# ATMega64_Breakout.net
KiCad netlist of a schematic drawn in Altium Designer
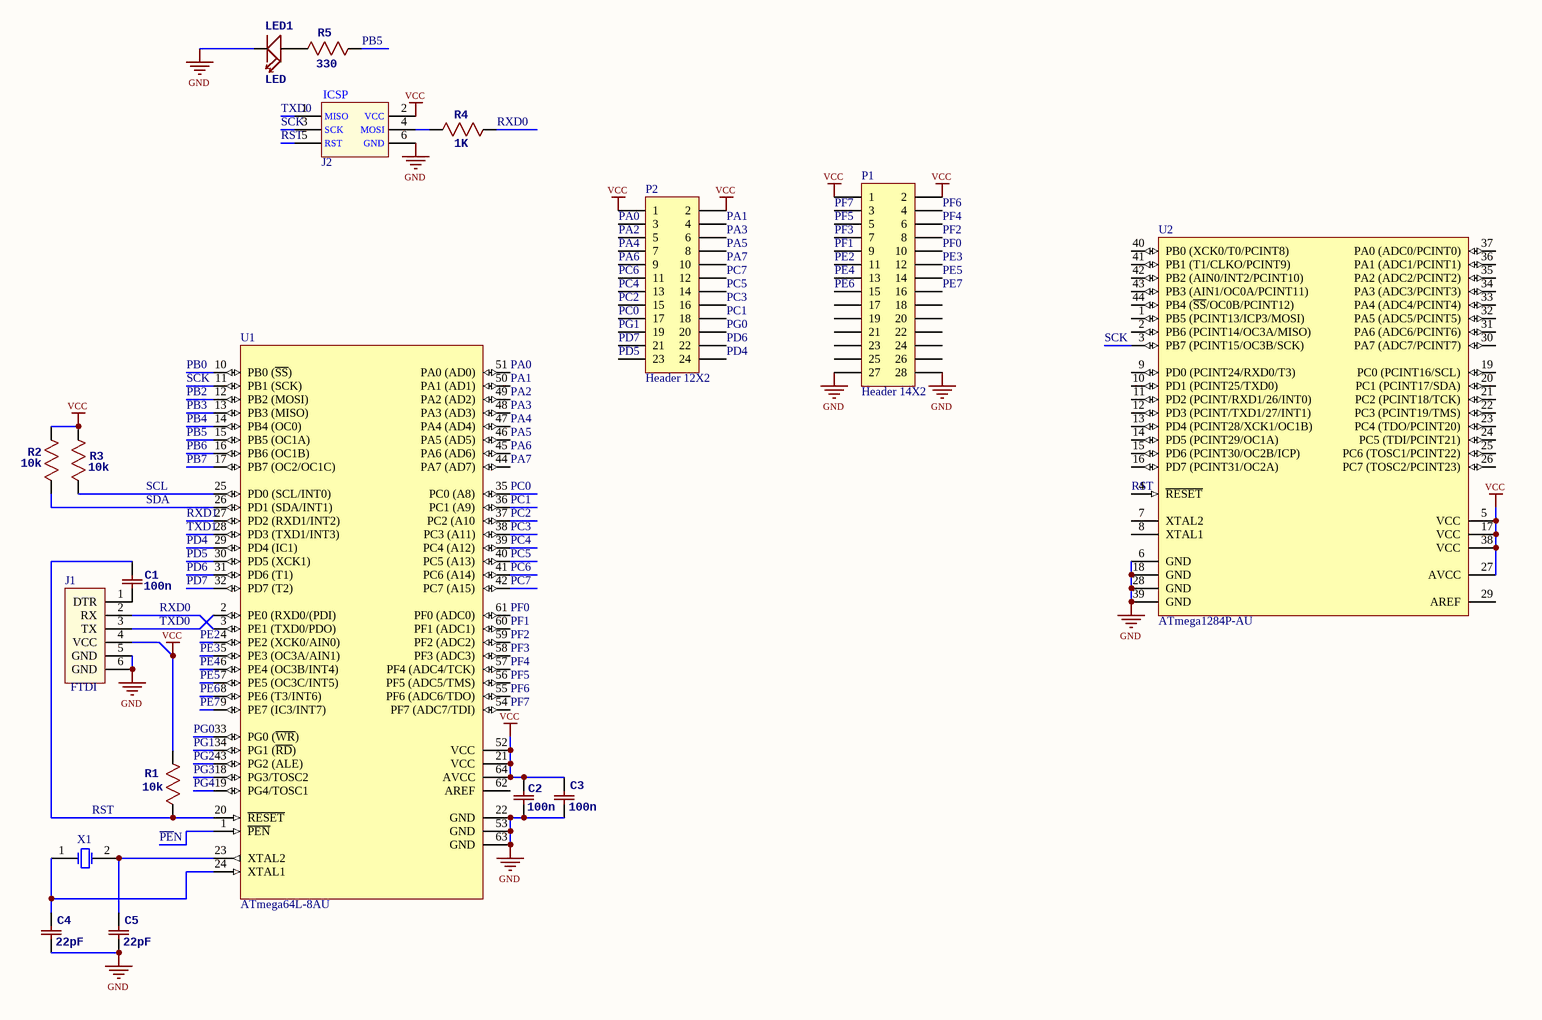
[diagram p0: ATMega64_Breakout.SchDoc]

(export (version "E")
  (design (tool "Eeschema 10.0.6"))
  (components
    (comp (ref "C1")
      (value "100n")
      (footprint "CAPC0805(2012)75_N")
      (fields (field (name "MPN") "U0805F104ZCT") (field (name "TOLERANCE") "-20/+80%"))
      (libsource (lib "Multicomp_By_element14_Batch_1") (part "U0805F104ZCT"))
    )
    (comp (ref "C2")
      (value "100n")
      (footprint "CAPC0805(2012)75_N")
      (fields (field (name "MPN") "U0805F104ZCT") (field (name "TOLERANCE") "-20/+80%"))
      (libsource (lib "Multicomp_By_element14_Batch_1") (part "U0805F104ZCT"))
    )
    (comp (ref "C3")
      (value "100n")
      (footprint "CAPC0805(2012)75_N")
      (fields (field (name "MPN") "U0805F104ZCT") (field (name "TOLERANCE") "-20/+80%"))
      (libsource (lib "Multicomp_By_element14_Batch_1") (part "U0805F104ZCT"))
    )
    (comp (ref "C4")
      (value "22pF")
      (footprint "CAPC0805(2012)75_N")
      (fields (field (name "MPN") "U0805F104ZCT") (field (name "TOLERANCE") "-20/+80%"))
      (libsource (lib "Multicomp_By_element14_Batch_1") (part "U0805F104ZCT"))
    )
    (comp (ref "C5")
      (value "22pF")
      (footprint "CAPC0805(2012)75_N")
      (fields (field (name "MPN") "U0805F104ZCT") (field (name "TOLERANCE") "-20/+80%"))
      (libsource (lib "Multicomp_By_element14_Batch_1") (part "U0805F104ZCT"))
    )
    (comp (ref "J1")
      (value "FTDI")
      (footprint "HDR1X6")
      (description "In-Circuit Serial Programming Header")
      (libsource (lib "AltiumIntegratedLibrary") (part "ICSP"))
    )
    (comp (ref "J2")
      (value "ICSP")
      (footprint "ICSP")
      (description "AVR ICSP")
      (libsource (lib "") (part "ICSP_1"))
    )
    (comp (ref "LED1")
      (value "LED")
      (footprint "LED-0805")
      (fields (field (name "MPN") "17-215SURC/S530-A2/TR8"))
      (libsource (lib "105848_revD3") (part "SMD-LED-CLEAR-RED(0805)"))
    )
    (comp (ref "P1")
      (value "Header 14X2")
      (footprint "HDR2X14")
      (description "Header, 14-Pin, Dual row")
      (fields (field (name "PUBLISHER") "Altium Limited"))
      (libsource (lib "Miscellaneous Connectors") (part "Header 14X2"))
    )
    (comp (ref "P2")
      (value "Header 12X2")
      (footprint "HDR2X12")
      (description "Header, 12-Pin, Dual row")
      (fields (field (name "PUBLISHER") "Altium Limited"))
      (libsource (lib "Miscellaneous Connectors") (part "Header 12X2"))
    )
    (comp (ref "R1")
      (value "10k")
      (footprint "RCHIP0805")
      (fields (field (name "MPN") "MC0.1W08051%10K") (field (name "TOLERANCE") "±1%"))
      (libsource (lib "Multicomp_By_element14_Batch_1") (part "MC0.1W08051%10K"))
    )
    (comp (ref "R2")
      (value "10k")
      (footprint "RCHIP0805")
      (fields (field (name "MPN") "MC0.1W08051%10K") (field (name "TOLERANCE") "±1%"))
      (libsource (lib "Multicomp_By_element14_Batch_1") (part "MC0.1W08051%10K"))
    )
    (comp (ref "R3")
      (value "10k")
      (footprint "RCHIP0805")
      (fields (field (name "MPN") "MC0.1W08051%10K") (field (name "TOLERANCE") "±1%"))
      (libsource (lib "Multicomp_By_element14_Batch_1") (part "MC0.1W08051%10K"))
    )
    (comp (ref "R4")
      (value "1K")
      (footprint "RCHIP0805")
      (fields (field (name "MPN") "MC0.1W08051%1K") (field (name "TOLERANCE") "±1%"))
      (libsource (lib "Multicomp_By_element14_Batch_1") (part "MC0.1W08051%1K"))
    )
    (comp (ref "R5")
      (value "330")
      (footprint "RCHIP0805")
      (fields (field (name "MPN") "MC0.1W08051%1K") (field (name "TOLERANCE") "±1%"))
      (libsource (lib "Multicomp_By_element14_Batch_1") (part "MC0.1W08051%1K"))
    )
    (comp (ref "U1")
      (value "ATmega64L-8AU")
      (footprint "64A_M")
      (libsource (lib "Atmel Microcontroller megaAVR") (part "ATmega64L-8AU"))
    )
    (comp (ref "U2")
      (value "ATmega1284P-AU")
      (footprint "44A_L")
      (libsource (lib "Atmel Microcontroller megaAVR") (part "ATmega1284P-AU"))
    )
    (comp (ref "X1")
      (value "XTAL")
      (footprint "CRES_SMT")
      (description "Crystal Oscillator")
      (fields (field (name "PUBLISHER") "Altium Limited"))
      (libsource (lib "Miscellaneous Devices") (part "XTAL"))
    )
  )
  (nets
    (net (code "1") (name "/PA0") (class "Default")
      (node (ref "P2") (pin "3") (pinfunction "3_3") (pintype "passive"))
      (node (ref "U1") (pin "51") (pinfunction "PA0_(AD0)_51") (pintype "bidirectional"))
    )
    (net (code "2") (name "/PA1") (class "Default")
      (node (ref "P2") (pin "4") (pinfunction "4_4") (pintype "passive"))
      (node (ref "U1") (pin "50") (pinfunction "PA1_(AD1)_50") (pintype "bidirectional"))
    )
    (net (code "3") (name "/PA2") (class "Default")
      (node (ref "P2") (pin "5") (pinfunction "5_5") (pintype "passive"))
      (node (ref "U1") (pin "49") (pinfunction "PA2_(AD2)_49") (pintype "bidirectional"))
    )
    (net (code "4") (name "/PA3") (class "Default")
      (node (ref "P2") (pin "6") (pinfunction "6_6") (pintype "passive"))
      (node (ref "U1") (pin "48") (pinfunction "PA3_(AD3)_48") (pintype "bidirectional"))
    )
    (net (code "5") (name "/PA4") (class "Default")
      (node (ref "P2") (pin "7") (pinfunction "7_7") (pintype "passive"))
      (node (ref "U1") (pin "47") (pinfunction "PA4_(AD4)_47") (pintype "bidirectional"))
    )
    (net (code "6") (name "/PA5") (class "Default")
      (node (ref "P2") (pin "8") (pinfunction "8_8") (pintype "passive"))
      (node (ref "U1") (pin "46") (pinfunction "PA5_(AD5)_46") (pintype "bidirectional"))
    )
    (net (code "7") (name "/PA6") (class "Default")
      (node (ref "P2") (pin "9") (pinfunction "9_9") (pintype "passive"))
      (node (ref "U1") (pin "45") (pinfunction "PA6_(AD6)_45") (pintype "bidirectional"))
    )
    (net (code "8") (name "/PA7") (class "Default")
      (node (ref "P2") (pin "10") (pinfunction "10_10") (pintype "passive"))
      (node (ref "U1") (pin "44") (pinfunction "PA7_(AD7)_44") (pintype "bidirectional"))
    )
    (net (code "9") (name "/PB0") (class "Default")
      (node (ref "U1") (pin "10") (pinfunction "PB0_(~{SS})_10") (pintype "bidirectional"))
    )
    (net (code "10") (name "/PB2") (class "Default")
      (node (ref "U1") (pin "12") (pinfunction "PB2_(MOSI)_12") (pintype "bidirectional"))
    )
    (net (code "11") (name "/PB3") (class "Default")
      (node (ref "U1") (pin "13") (pinfunction "PB3_(MISO)_13") (pintype "bidirectional"))
    )
    (net (code "12") (name "/PB4") (class "Default")
      (node (ref "U1") (pin "14") (pinfunction "PB4_(OC0)_14") (pintype "bidirectional"))
    )
    (net (code "13") (name "/PB5") (class "Default")
      (node (ref "R5") (pin "2") (pinfunction "R2_2") (pintype "passive"))
      (node (ref "U1") (pin "15") (pinfunction "PB5_(OC1A)_15") (pintype "bidirectional"))
    )
    (net (code "14") (name "/PB6") (class "Default")
      (node (ref "U1") (pin "16") (pinfunction "PB6_(OC1B)_16") (pintype "bidirectional"))
    )
    (net (code "15") (name "/PB7") (class "Default")
      (node (ref "U1") (pin "17") (pinfunction "PB7_(OC2/OC1C)_17") (pintype "bidirectional"))
    )
    (net (code "16") (name "/PC0") (class "Default")
      (node (ref "P2") (pin "17") (pinfunction "17_17") (pintype "passive"))
      (node (ref "U1") (pin "35") (pinfunction "PC0_(A8)_35") (pintype "bidirectional"))
    )
    (net (code "17") (name "/PC1") (class "Default")
      (node (ref "P2") (pin "18") (pinfunction "18_18") (pintype "passive"))
      (node (ref "U1") (pin "36") (pinfunction "PC1_(A9)_36") (pintype "bidirectional"))
    )
    (net (code "18") (name "/PC2") (class "Default")
      (node (ref "P2") (pin "15") (pinfunction "15_15") (pintype "passive"))
      (node (ref "U1") (pin "37") (pinfunction "PC2_(A10_37") (pintype "bidirectional"))
    )
    (net (code "19") (name "/PC3") (class "Default")
      (node (ref "P2") (pin "16") (pinfunction "16_16") (pintype "passive"))
      (node (ref "U1") (pin "38") (pinfunction "PC3_(A11)_38") (pintype "bidirectional"))
    )
    (net (code "20") (name "/PC4") (class "Default")
      (node (ref "P2") (pin "13") (pinfunction "13_13") (pintype "passive"))
      (node (ref "U1") (pin "39") (pinfunction "PC4_(A12)_39") (pintype "bidirectional"))
    )
    (net (code "21") (name "/PC5") (class "Default")
      (node (ref "P2") (pin "14") (pinfunction "14_14") (pintype "passive"))
      (node (ref "U1") (pin "40") (pinfunction "PC5_(A13)_40") (pintype "bidirectional"))
    )
    (net (code "22") (name "/PC6") (class "Default")
      (node (ref "P2") (pin "11") (pinfunction "11_11") (pintype "passive"))
      (node (ref "U1") (pin "41") (pinfunction "PC6_(A14)_41") (pintype "bidirectional"))
    )
    (net (code "23") (name "/PC7") (class "Default")
      (node (ref "P2") (pin "12") (pinfunction "12_12") (pintype "passive"))
      (node (ref "U1") (pin "42") (pinfunction "PC7_(A15)_42") (pintype "bidirectional"))
    )
    (net (code "24") (name "/PD4") (class "Default")
      (node (ref "P2") (pin "24") (pinfunction "24_24") (pintype "passive"))
      (node (ref "U1") (pin "29") (pinfunction "PD4_(IC1)_29") (pintype "bidirectional"))
    )
    (net (code "25") (name "/PD5") (class "Default")
      (node (ref "P2") (pin "23") (pinfunction "23_23") (pintype "passive"))
      (node (ref "U1") (pin "30") (pinfunction "PD5_(XCK1)_30") (pintype "bidirectional"))
    )
    (net (code "26") (name "/PD6") (class "Default")
      (node (ref "P2") (pin "22") (pinfunction "22_22") (pintype "passive"))
      (node (ref "U1") (pin "31") (pinfunction "PD6_(T1)_31") (pintype "bidirectional"))
    )
    (net (code "27") (name "/PD7") (class "Default")
      (node (ref "P2") (pin "21") (pinfunction "21_21") (pintype "passive"))
      (node (ref "U1") (pin "32") (pinfunction "PD7_(T2)_32") (pintype "bidirectional"))
    )
    (net (code "28") (name "/PE2") (class "Default")
      (node (ref "P1") (pin "11") (pinfunction "11_11") (pintype "passive"))
      (node (ref "U1") (pin "4") (pinfunction "PE2_(XCK0/AIN0)_4") (pintype "bidirectional"))
    )
    (net (code "29") (name "/PE3") (class "Default")
      (node (ref "P1") (pin "12") (pinfunction "12_12") (pintype "passive"))
      (node (ref "U1") (pin "5") (pinfunction "PE3_(OC3A/AIN1)_5") (pintype "bidirectional"))
    )
    (net (code "30") (name "/PE4") (class "Default")
      (node (ref "P1") (pin "13") (pinfunction "13_13") (pintype "passive"))
      (node (ref "U1") (pin "6") (pinfunction "PE4_(OC3B/INT4)_6") (pintype "bidirectional"))
    )
    (net (code "31") (name "/PE5") (class "Default")
      (node (ref "P1") (pin "14") (pinfunction "14_14") (pintype "passive"))
      (node (ref "U1") (pin "7") (pinfunction "PE5_(OC3C/INT5)_7") (pintype "bidirectional"))
    )
    (net (code "32") (name "/PE6") (class "Default")
      (node (ref "P1") (pin "15") (pinfunction "15_15") (pintype "passive"))
      (node (ref "U1") (pin "8") (pinfunction "PE6_(T3/INT6)_8") (pintype "bidirectional"))
    )
    (net (code "33") (name "/PE7") (class "Default")
      (node (ref "P1") (pin "16") (pinfunction "16_16") (pintype "passive"))
      (node (ref "U1") (pin "9") (pinfunction "PE7_(IC3/INT7)_9") (pintype "bidirectional"))
    )
    (net (code "34") (name "/PF0") (class "Default")
      (node (ref "P1") (pin "10") (pinfunction "10_10") (pintype "passive"))
      (node (ref "U1") (pin "61") (pinfunction "PF0_(ADC0)_61") (pintype "bidirectional"))
    )
    (net (code "35") (name "/PF1") (class "Default")
      (node (ref "P1") (pin "9") (pinfunction "9_9") (pintype "passive"))
      (node (ref "U1") (pin "60") (pinfunction "PF1_(ADC1)_60") (pintype "bidirectional"))
    )
    (net (code "36") (name "/PF2") (class "Default")
      (node (ref "P1") (pin "8") (pinfunction "8_8") (pintype "passive"))
      (node (ref "U1") (pin "59") (pinfunction "PF2_(ADC2)_59") (pintype "bidirectional"))
    )
    (net (code "37") (name "/PF3") (class "Default")
      (node (ref "P1") (pin "7") (pinfunction "7_7") (pintype "passive"))
      (node (ref "U1") (pin "58") (pinfunction "PF3_(ADC3)_58") (pintype "bidirectional"))
    )
    (net (code "38") (name "/PF4") (class "Default")
      (node (ref "P1") (pin "6") (pinfunction "6_6") (pintype "passive"))
      (node (ref "U1") (pin "57") (pinfunction "PF4_(ADC4/TCK)_57") (pintype "bidirectional"))
    )
    (net (code "39") (name "/PF5") (class "Default")
      (node (ref "P1") (pin "5") (pinfunction "5_5") (pintype "passive"))
      (node (ref "U1") (pin "56") (pinfunction "PF5_(ADC5/TMS)_56") (pintype "bidirectional"))
    )
    (net (code "40") (name "/PF6") (class "Default")
      (node (ref "P1") (pin "4") (pinfunction "4_4") (pintype "passive"))
      (node (ref "U1") (pin "55") (pinfunction "PF6_(ADC6/TDO)_55") (pintype "bidirectional"))
    )
    (net (code "41") (name "/PF7") (class "Default")
      (node (ref "P1") (pin "3") (pinfunction "3_3") (pintype "passive"))
      (node (ref "U1") (pin "54") (pinfunction "PF7_(ADC7/TDI)_54") (pintype "bidirectional"))
    )
    (net (code "42") (name "/PG0") (class "Default")
      (node (ref "P2") (pin "20") (pinfunction "20_20") (pintype "passive"))
      (node (ref "U1") (pin "33") (pinfunction "PG0_(~{WR})_33") (pintype "bidirectional"))
    )
    (net (code "43") (name "/PG1") (class "Default")
      (node (ref "P2") (pin "19") (pinfunction "19_19") (pintype "passive"))
      (node (ref "U1") (pin "34") (pinfunction "PG1_(~{RD})_34") (pintype "bidirectional"))
    )
    (net (code "44") (name "/PG2") (class "Default")
      (node (ref "U1") (pin "43") (pinfunction "PG2_(ALE)_43") (pintype "bidirectional"))
    )
    (net (code "45") (name "/PG3") (class "Default")
      (node (ref "U1") (pin "18") (pinfunction "PG3/TOSC2_18") (pintype "bidirectional"))
    )
    (net (code "46") (name "/PG4") (class "Default")
      (node (ref "U1") (pin "19") (pinfunction "PG4/TOSC1_19") (pintype "bidirectional"))
    )
    (net (code "47") (name "/RST") (class "Default")
      (node (ref "C1") (pin "2") (pinfunction "C2_2") (pintype "passive"))
      (node (ref "J2") (pin "5") (pinfunction "RST_5") (pintype "passive"))
      (node (ref "R1") (pin "2") (pinfunction "R2_2") (pintype "passive"))
      (node (ref "U1") (pin "20") (pinfunction "~{RESET}_20") (pintype "input"))
      (node (ref "U2") (pin "4") (pinfunction "~{RESET}_4") (pintype "input"))
    )
    (net (code "48") (name "/RXD0") (class "Default")
      (node (ref "J1") (pin "2") (pinfunction "RX_2") (pintype "passive"))
      (node (ref "R4") (pin "1") (pinfunction "R1_1") (pintype "passive"))
      (node (ref "U1") (pin "3") (pinfunction "PE1_(TXD0/PDO)_3") (pintype "bidirectional"))
    )
    (net (code "49") (name "/RXD1") (class "Default")
      (node (ref "U1") (pin "27") (pinfunction "PD2_(RXD1/INT2)_27") (pintype "bidirectional"))
    )
    (net (code "50") (name "/SCK") (class "Default")
      (node (ref "J2") (pin "3") (pinfunction "SCK_3") (pintype "passive"))
      (node (ref "U1") (pin "11") (pinfunction "PB1_(SCK)_11") (pintype "bidirectional"))
      (node (ref "U2") (pin "3") (pinfunction "PB7_(PCINT15/OC3B/SCK)_3") (pintype "bidirectional"))
    )
    (net (code "51") (name "/SCL") (class "Default")
      (node (ref "R3") (pin "2") (pinfunction "R2_2") (pintype "passive"))
      (node (ref "U1") (pin "25") (pinfunction "PD0_(SCL/INT0)_25") (pintype "bidirectional"))
    )
    (net (code "52") (name "/SDA") (class "Default")
      (node (ref "R2") (pin "2") (pinfunction "R2_2") (pintype "passive"))
      (node (ref "U1") (pin "26") (pinfunction "PD1_(SDA/INT1)_26") (pintype "bidirectional"))
    )
    (net (code "53") (name "/TXD0") (class "Default")
      (node (ref "J1") (pin "3") (pinfunction "TX_3") (pintype "passive"))
      (node (ref "J2") (pin "1") (pinfunction "MISO_1") (pintype "passive"))
      (node (ref "U1") (pin "2") (pinfunction "PE0_(RXD0/(PDI)_2") (pintype "bidirectional"))
    )
    (net (code "54") (name "/TXD1") (class "Default")
      (node (ref "U1") (pin "28") (pinfunction "PD3_(TXD1/INT3)_28") (pintype "bidirectional"))
    )
    (net (code "55") (name "/~{PE}N") (class "Default")
      (node (ref "U1") (pin "1") (pinfunction "~{PEN}_1") (pintype "input"))
    )
    (net (code "56") (name "GND") (class "Default")
      (node (ref "C2") (pin "1") (pinfunction "C1_1") (pintype "passive"))
      (node (ref "C3") (pin "1") (pinfunction "C1_1") (pintype "passive"))
      (node (ref "C4") (pin "1") (pinfunction "C1_1") (pintype "passive"))
      (node (ref "C5") (pin "1") (pinfunction "C1_1") (pintype "passive"))
      (node (ref "J1") (pin "5") (pinfunction "GND_5") (pintype "passive"))
      (node (ref "J1") (pin "6") (pinfunction "GND_6") (pintype "passive"))
      (node (ref "J2") (pin "6") (pinfunction "GND_6") (pintype "passive"))
      (node (ref "LED1") (pin "-") (pinfunction "-_-") (pintype "passive"))
      (node (ref "P1") (pin "27") (pinfunction "27_27") (pintype "passive"))
      (node (ref "P1") (pin "28") (pinfunction "28_28") (pintype "passive"))
      (node (ref "U1") (pin "22") (pinfunction "GND_22") (pintype "power_in"))
      (node (ref "U1") (pin "53") (pinfunction "GND_53") (pintype "power_in"))
      (node (ref "U1") (pin "63") (pinfunction "GND_63") (pintype "power_in"))
      (node (ref "U2") (pin "18") (pinfunction "GND_18") (pintype "power_in"))
      (node (ref "U2") (pin "28") (pinfunction "GND_28") (pintype "power_in"))
      (node (ref "U2") (pin "39") (pinfunction "GND_39") (pintype "power_in"))
      (node (ref "U2") (pin "6") (pinfunction "GND_6") (pintype "power_in"))
    )
    (net (code "57") (name "Net-(C1-C1)") (class "Default")
      (node (ref "C1") (pin "1") (pinfunction "C1_1") (pintype "passive"))
      (node (ref "J1") (pin "1") (pinfunction "DTR_1") (pintype "passive"))
    )
    (net (code "58") (name "Net-(C4-C2)") (class "Default")
      (node (ref "C4") (pin "2") (pinfunction "C2_2") (pintype "passive"))
      (node (ref "U1") (pin "24") (pinfunction "XTAL1_24") (pintype "input"))
      (node (ref "X1") (pin "1") (pinfunction "OSC1_1") (pintype "passive"))
    )
    (net (code "59") (name "Net-(C5-C2)") (class "Default")
      (node (ref "C5") (pin "2") (pinfunction "C2_2") (pintype "passive"))
      (node (ref "U1") (pin "23") (pinfunction "XTAL2_23") (pintype "output"))
      (node (ref "X1") (pin "2") (pinfunction "OSC2_2") (pintype "passive"))
    )
    (net (code "60") (name "Net-(J2-MOSI)") (class "Default")
      (node (ref "J2") (pin "4") (pinfunction "MOSI_4") (pintype "passive"))
      (node (ref "R4") (pin "2") (pinfunction "R2_2") (pintype "passive"))
    )
    (net (code "61") (name "Net-(R5-R1)") (class "Default")
      (node (ref "LED1") (pin "+") (pinfunction "+_+") (pintype "passive"))
      (node (ref "R5") (pin "1") (pinfunction "R1_1") (pintype "passive"))
    )
    (net (code "62") (name "VCC") (class "Default")
      (node (ref "C2") (pin "2") (pinfunction "C2_2") (pintype "passive"))
      (node (ref "C3") (pin "2") (pinfunction "C2_2") (pintype "passive"))
      (node (ref "J1") (pin "4") (pinfunction "VCC_4") (pintype "passive"))
      (node (ref "J2") (pin "2") (pinfunction "VCC_2") (pintype "passive"))
      (node (ref "P1") (pin "1") (pinfunction "1_1") (pintype "passive"))
      (node (ref "P1") (pin "2") (pinfunction "2_2") (pintype "passive"))
      (node (ref "P2") (pin "1") (pinfunction "1_1") (pintype "passive"))
      (node (ref "P2") (pin "2") (pinfunction "2_2") (pintype "passive"))
      (node (ref "R1") (pin "1") (pinfunction "R1_1") (pintype "passive"))
      (node (ref "R2") (pin "1") (pinfunction "R1_1") (pintype "passive"))
      (node (ref "R3") (pin "1") (pinfunction "R1_1") (pintype "passive"))
      (node (ref "U1") (pin "21") (pinfunction "VCC_21") (pintype "power_in"))
      (node (ref "U1") (pin "52") (pinfunction "VCC_52") (pintype "power_in"))
      (node (ref "U1") (pin "64") (pinfunction "AVCC_64") (pintype "power_in"))
      (node (ref "U2") (pin "17") (pinfunction "VCC_17") (pintype "power_in"))
      (node (ref "U2") (pin "27") (pinfunction "AVCC_27") (pintype "power_in"))
      (node (ref "U2") (pin "38") (pinfunction "VCC_38") (pintype "power_in"))
      (node (ref "U2") (pin "5") (pinfunction "VCC_5") (pintype "power_in"))
    )
    (net (code "63") (name "unconnected-(P1-Pad17)") (class "Default")
      (node (ref "P1") (pin "17") (pinfunction "17_17") (pintype "passive"))
    )
    (net (code "64") (name "unconnected-(P1-Pad18)") (class "Default")
      (node (ref "P1") (pin "18") (pinfunction "18_18") (pintype "passive"))
    )
    (net (code "65") (name "unconnected-(P1-Pad19)") (class "Default")
      (node (ref "P1") (pin "19") (pinfunction "19_19") (pintype "passive"))
    )
    (net (code "66") (name "unconnected-(P1-Pad20)") (class "Default")
      (node (ref "P1") (pin "20") (pinfunction "20_20") (pintype "passive"))
    )
    (net (code "67") (name "unconnected-(P1-Pad21)") (class "Default")
      (node (ref "P1") (pin "21") (pinfunction "21_21") (pintype "passive"))
    )
    (net (code "68") (name "unconnected-(P1-Pad22)") (class "Default")
      (node (ref "P1") (pin "22") (pinfunction "22_22") (pintype "passive"))
    )
    (net (code "69") (name "unconnected-(P1-Pad23)") (class "Default")
      (node (ref "P1") (pin "23") (pinfunction "23_23") (pintype "passive"))
    )
    (net (code "70") (name "unconnected-(P1-Pad24)") (class "Default")
      (node (ref "P1") (pin "24") (pinfunction "24_24") (pintype "passive"))
    )
    (net (code "71") (name "unconnected-(P1-Pad25)") (class "Default")
      (node (ref "P1") (pin "25") (pinfunction "25_25") (pintype "passive"))
    )
    (net (code "72") (name "unconnected-(P1-Pad26)") (class "Default")
      (node (ref "P1") (pin "26") (pinfunction "26_26") (pintype "passive"))
    )
    (net (code "73") (name "unconnected-(U1-AREF-Pad62)") (class "Default")
      (node (ref "U1") (pin "62") (pinfunction "AREF_62") (pintype "passive"))
    )
    (net (code "74") (name "unconnected-(U2-AREF-Pad29)") (class "Default")
      (node (ref "U2") (pin "29") (pinfunction "AREF_29") (pintype "power_in"))
    )
    (net (code "75") (name "unconnected-(U2-PA0_(ADC0{slash}PCINT0)-Pad37)") (class "Default")
      (node (ref "U2") (pin "37") (pinfunction "PA0_(ADC0/PCINT0)_37") (pintype "bidirectional"))
    )
    (net (code "76") (name "unconnected-(U2-PA1_(ADC1{slash}PCINT1)-Pad36)") (class "Default")
      (node (ref "U2") (pin "36") (pinfunction "PA1_(ADC1/PCINT1)_36") (pintype "bidirectional"))
    )
    (net (code "77") (name "unconnected-(U2-PA2_(ADC2{slash}PCINT2)-Pad35)") (class "Default")
      (node (ref "U2") (pin "35") (pinfunction "PA2_(ADC2/PCINT2)_35") (pintype "bidirectional"))
    )
    (net (code "78") (name "unconnected-(U2-PA3_(ADC3{slash}PCINT3)-Pad34)") (class "Default")
      (node (ref "U2") (pin "34") (pinfunction "PA3_(ADC3/PCINT3)_34") (pintype "bidirectional"))
    )
    (net (code "79") (name "unconnected-(U2-PA4_(ADC4{slash}PCINT4)-Pad33)") (class "Default")
      (node (ref "U2") (pin "33") (pinfunction "PA4_(ADC4/PCINT4)_33") (pintype "bidirectional"))
    )
    (net (code "80") (name "unconnected-(U2-PA5_(ADC5{slash}PCINT5)-Pad32)") (class "Default")
      (node (ref "U2") (pin "32") (pinfunction "PA5_(ADC5/PCINT5)_32") (pintype "bidirectional"))
    )
    (net (code "81") (name "unconnected-(U2-PA6_(ADC6{slash}PCINT6)-Pad31)") (class "Default")
      (node (ref "U2") (pin "31") (pinfunction "PA6_(ADC6/PCINT6)_31") (pintype "bidirectional"))
    )
    (net (code "82") (name "unconnected-(U2-PA7_(ADC7{slash}PCINT7)-Pad30)") (class "Default")
      (node (ref "U2") (pin "30") (pinfunction "PA7_(ADC7/PCINT7)_30") (pintype "bidirectional"))
    )
    (net (code "83") (name "unconnected-(U2-PB0_(XCK0{slash}T0{slash}PCINT8)-Pad40)") (class "Default")
      (node (ref "U2") (pin "40") (pinfunction "PB0_(XCK0/T0/PCINT8)_40") (pintype "bidirectional"))
    )
    (net (code "84") (name "unconnected-(U2-PB1_(T1{slash}CLKO{slash}PCINT9)-Pad41)") (class "Default")
      (node (ref "U2") (pin "41") (pinfunction "PB1_(T1/CLKO/PCINT9)_41") (pintype "bidirectional"))
    )
    (net (code "85") (name "unconnected-(U2-PB2_(AIN0{slash}INT2{slash}PCINT10)-Pad42)") (class "Default")
      (node (ref "U2") (pin "42") (pinfunction "PB2_(AIN0/INT2/PCINT10)_42") (pintype "bidirectional"))
    )
    (net (code "86") (name "unconnected-(U2-PB3_(AIN1{slash}OC0A{slash}PCINT11)-Pad43)") (class "Default")
      (node (ref "U2") (pin "43") (pinfunction "PB3_(AIN1/OC0A/PCINT11)_43") (pintype "bidirectional"))
    )
    (net (code "87") (name "unconnected-(U2-PB4_(~{SS}{slash}OC0B{slash}PCINT12)-Pad44)") (class "Default")
      (node (ref "U2") (pin "44") (pinfunction "PB4_(~{SS}/OC0B/PCINT12)_44") (pintype "bidirectional"))
    )
    (net (code "88") (name "unconnected-(U2-PB5_(PCINT13{slash}ICP3{slash}MOSI)-Pad1)") (class "Default")
      (node (ref "U2") (pin "1") (pinfunction "PB5_(PCINT13/ICP3/MOSI)_1") (pintype "bidirectional"))
    )
    (net (code "89") (name "unconnected-(U2-PB6_(PCINT14{slash}OC3A{slash}MISO)-Pad2)") (class "Default")
      (node (ref "U2") (pin "2") (pinfunction "PB6_(PCINT14/OC3A/MISO)_2") (pintype "bidirectional"))
    )
    (net (code "90") (name "unconnected-(U2-PC0_(PCINT16{slash}SCL)-Pad19)") (class "Default")
      (node (ref "U2") (pin "19") (pinfunction "PC0_(PCINT16/SCL)_19") (pintype "bidirectional"))
    )
    (net (code "91") (name "unconnected-(U2-PC1_(PCINT17{slash}SDA)-Pad20)") (class "Default")
      (node (ref "U2") (pin "20") (pinfunction "PC1_(PCINT17/SDA)_20") (pintype "bidirectional"))
    )
    (net (code "92") (name "unconnected-(U2-PC2_(PCINT18{slash}TCK)-Pad21)") (class "Default")
      (node (ref "U2") (pin "21") (pinfunction "PC2_(PCINT18/TCK)_21") (pintype "bidirectional"))
    )
    (net (code "93") (name "unconnected-(U2-PC3_(PCINT19{slash}TMS)-Pad22)") (class "Default")
      (node (ref "U2") (pin "22") (pinfunction "PC3_(PCINT19/TMS)_22") (pintype "bidirectional"))
    )
    (net (code "94") (name "unconnected-(U2-PC4_(TDO{slash}PCINT20)-Pad23)") (class "Default")
      (node (ref "U2") (pin "23") (pinfunction "PC4_(TDO/PCINT20)_23") (pintype "bidirectional"))
    )
    (net (code "95") (name "unconnected-(U2-PC5_(TDI{slash}PCINT21)-Pad24)") (class "Default")
      (node (ref "U2") (pin "24") (pinfunction "PC5_(TDI/PCINT21)_24") (pintype "bidirectional"))
    )
    (net (code "96") (name "unconnected-(U2-PC6_(TOSC1{slash}PCINT22)-Pad25)") (class "Default")
      (node (ref "U2") (pin "25") (pinfunction "PC6_(TOSC1/PCINT22)_25") (pintype "bidirectional"))
    )
    (net (code "97") (name "unconnected-(U2-PC7_(TOSC2{slash}PCINT23)-Pad26)") (class "Default")
      (node (ref "U2") (pin "26") (pinfunction "PC7_(TOSC2/PCINT23)_26") (pintype "bidirectional"))
    )
    (net (code "98") (name "unconnected-(U2-PD0_(PCINT24{slash}RXD0{slash}T3)-Pad9)") (class "Default")
      (node (ref "U2") (pin "9") (pinfunction "PD0_(PCINT24/RXD0/T3)_9") (pintype "bidirectional"))
    )
    (net (code "99") (name "unconnected-(U2-PD1_(PCINT25{slash}TXD0)-Pad10)") (class "Default")
      (node (ref "U2") (pin "10") (pinfunction "PD1_(PCINT25/TXD0)_10") (pintype "bidirectional"))
    )
    (net (code "100") (name "unconnected-(U2-PD2_(PCINT{slash}RXD1{slash}26{slash}INT0)-Pad11)") (class "Default")
      (node (ref "U2") (pin "11") (pinfunction "PD2_(PCINT/RXD1/26/INT0)_11") (pintype "bidirectional"))
    )
    (net (code "101") (name "unconnected-(U2-PD3_(PCINT{slash}TXD1{slash}27{slash}INT1)-Pad12)") (class "Default")
      (node (ref "U2") (pin "12") (pinfunction "PD3_(PCINT/TXD1/27/INT1)_12") (pintype "bidirectional"))
    )
    (net (code "102") (name "unconnected-(U2-PD4_(PCINT28{slash}XCK1{slash}OC1B)-Pad13)") (class "Default")
      (node (ref "U2") (pin "13") (pinfunction "PD4_(PCINT28/XCK1/OC1B)_13") (pintype "bidirectional"))
    )
    (net (code "103") (name "unconnected-(U2-PD5_(PCINT29{slash}OC1A)-Pad14)") (class "Default")
      (node (ref "U2") (pin "14") (pinfunction "PD5_(PCINT29/OC1A)_14") (pintype "bidirectional"))
    )
    (net (code "104") (name "unconnected-(U2-PD6_(PCINT30{slash}OC2B{slash}ICP)-Pad15)") (class "Default")
      (node (ref "U2") (pin "15") (pinfunction "PD6_(PCINT30/OC2B/ICP)_15") (pintype "bidirectional"))
    )
    (net (code "105") (name "unconnected-(U2-PD7_(PCINT31{slash}OC2A)-Pad16)") (class "Default")
      (node (ref "U2") (pin "16") (pinfunction "PD7_(PCINT31/OC2A)_16") (pintype "bidirectional"))
    )
    (net (code "106") (name "unconnected-(U2-XTAL1-Pad8)") (class "Default")
      (node (ref "U2") (pin "8") (pinfunction "XTAL1_8") (pintype "passive"))
    )
    (net (code "107") (name "unconnected-(U2-XTAL2-Pad7)") (class "Default")
      (node (ref "U2") (pin "7") (pinfunction "XTAL2_7") (pintype "passive"))
    )
  )
)
